# frontpanel.net
KiCad netlist of a schematic drawn in EAGLE
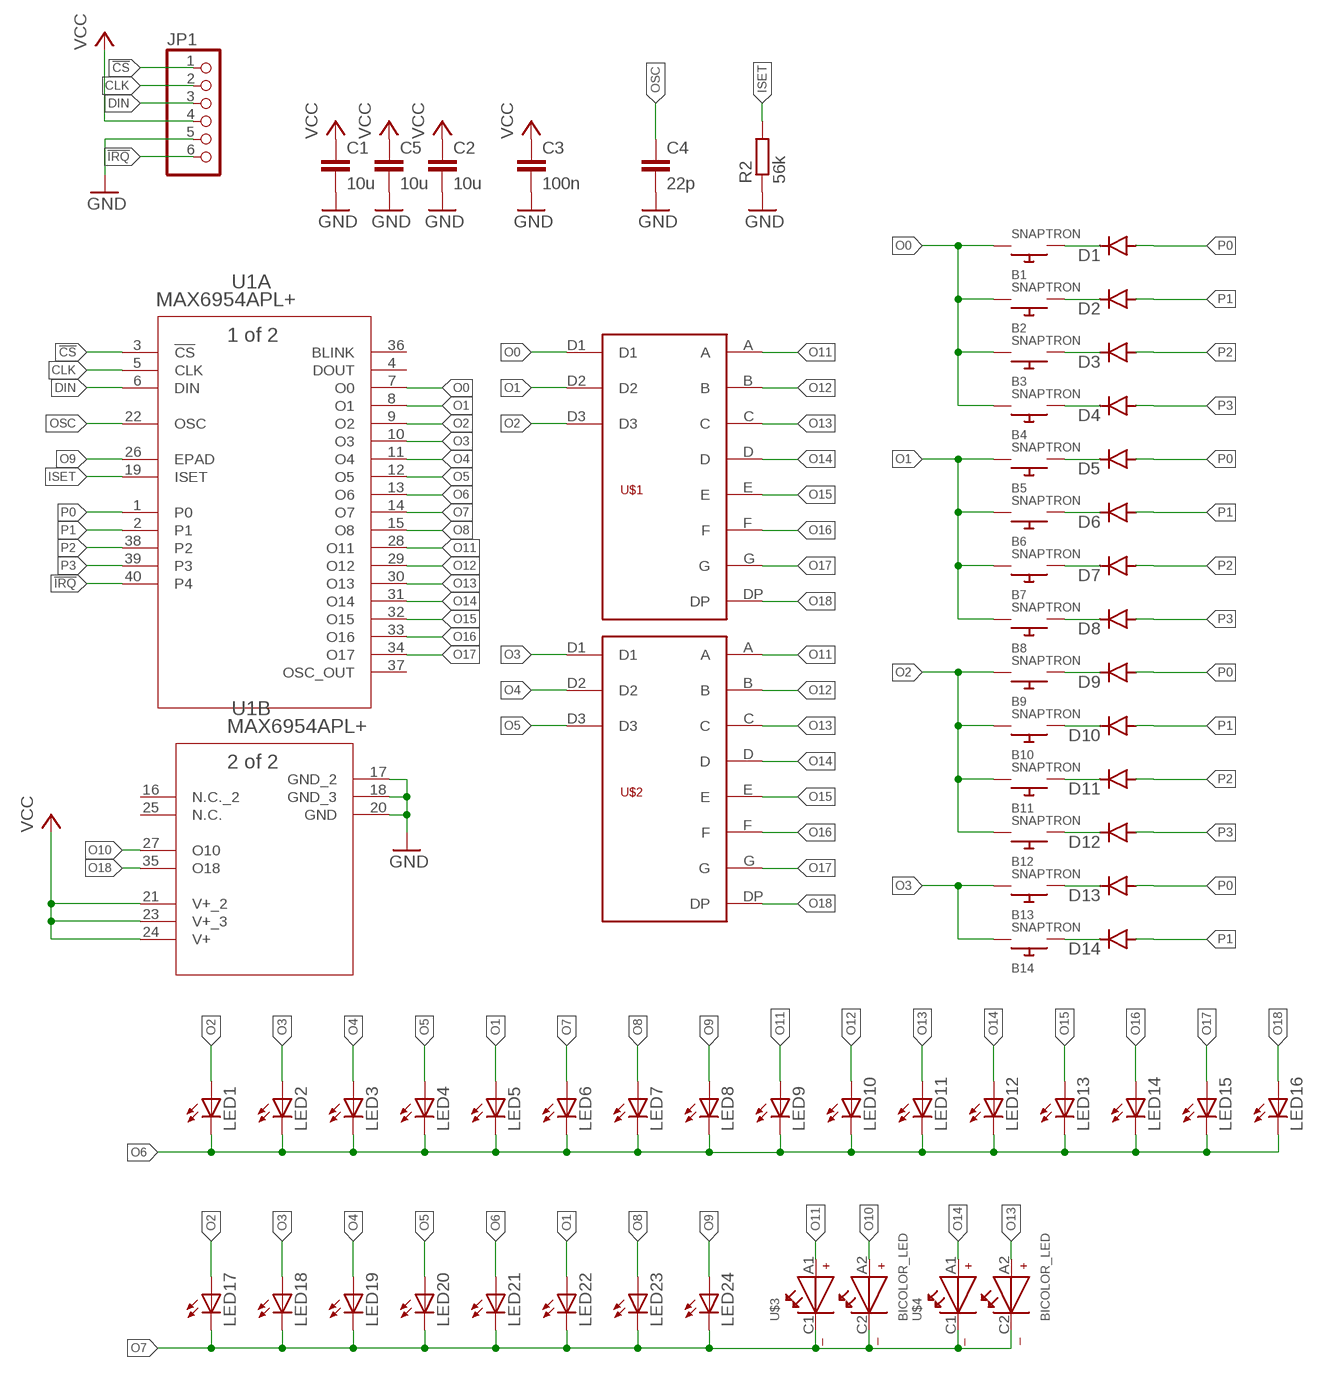
[diagram p0: schematic, sheet 1]

(export (version "E")
  (design (tool "Eeschema 10.0.6"))
  (components
    (comp (ref "B1")
      (value "SNAPTRON")
      (footprint "eagle-import:SNAPTRON-8.5")
      (libsource (lib "eagle-import") (part "SNAPTRON"))
    )
    (comp (ref "B2")
      (value "SNAPTRON")
      (footprint "eagle-import:SNAPTRON-8.5")
      (libsource (lib "eagle-import") (part "SNAPTRON"))
    )
    (comp (ref "B3")
      (value "SNAPTRON")
      (footprint "eagle-import:SNAPTRON-8.5")
      (libsource (lib "eagle-import") (part "SNAPTRON"))
    )
    (comp (ref "B4")
      (value "SNAPTRON")
      (footprint "eagle-import:SNAPTRON-8.5")
      (libsource (lib "eagle-import") (part "SNAPTRON"))
    )
    (comp (ref "B5")
      (value "SNAPTRON")
      (footprint "eagle-import:SNAPTRON-8.5")
      (libsource (lib "eagle-import") (part "SNAPTRON"))
    )
    (comp (ref "B6")
      (value "SNAPTRON")
      (footprint "eagle-import:SNAPTRON-8.5")
      (libsource (lib "eagle-import") (part "SNAPTRON"))
    )
    (comp (ref "B7")
      (value "SNAPTRON")
      (footprint "eagle-import:SNAPTRON-8.5")
      (libsource (lib "eagle-import") (part "SNAPTRON"))
    )
    (comp (ref "B8")
      (value "SNAPTRON")
      (footprint "eagle-import:SNAPTRON-8.5")
      (libsource (lib "eagle-import") (part "SNAPTRON"))
    )
    (comp (ref "B9")
      (value "SNAPTRON")
      (footprint "eagle-import:SNAPTRON-8.5")
      (libsource (lib "eagle-import") (part "SNAPTRON"))
    )
    (comp (ref "B10")
      (value "SNAPTRON")
      (footprint "eagle-import:SNAPTRON-8.5")
      (libsource (lib "eagle-import") (part "SNAPTRON"))
    )
    (comp (ref "B11")
      (value "SNAPTRON")
      (footprint "eagle-import:SNAPTRON-8.5")
      (libsource (lib "eagle-import") (part "SNAPTRON"))
    )
    (comp (ref "B12")
      (value "SNAPTRON")
      (footprint "eagle-import:SNAPTRON-8.5")
      (libsource (lib "eagle-import") (part "SNAPTRON"))
    )
    (comp (ref "B13")
      (value "SNAPTRON")
      (footprint "eagle-import:SNAPTRON-8.5")
      (libsource (lib "eagle-import") (part "SNAPTRON"))
    )
    (comp (ref "B14")
      (value "SNAPTRON")
      (footprint "eagle-import:SNAPTRON-8.5")
      (libsource (lib "eagle-import") (part "SNAPTRON"))
    )
    (comp (ref "C1")
      (value "10u")
      (footprint "eagle-import:C0805")
      (libsource (lib "eagle-import") (part "C-EUC0805"))
    )
    (comp (ref "C2")
      (value "10u")
      (footprint "eagle-import:C0805")
      (libsource (lib "eagle-import") (part "C-EUC0805"))
    )
    (comp (ref "C3")
      (value "100n")
      (footprint "eagle-import:C0805")
      (libsource (lib "eagle-import") (part "C-EUC0805"))
    )
    (comp (ref "C4")
      (value "22p")
      (footprint "eagle-import:C0805")
      (libsource (lib "eagle-import") (part "C-EUC0805"))
    )
    (comp (ref "C5")
      (value "10u")
      (footprint "eagle-import:C0805")
      (libsource (lib "eagle-import") (part "C-EUC0805"))
    )
    (comp (ref "D1")
      (value "1N4148DO35-10")
      (footprint "eagle-import:DO35-10")
      (libsource (lib "eagle-import") (part "1N4148DO35-10"))
    )
    (comp (ref "D2")
      (value "1N4148DO35-10")
      (footprint "eagle-import:DO35-10")
      (libsource (lib "eagle-import") (part "1N4148DO35-10"))
    )
    (comp (ref "D3")
      (value "1N4148DO35-10")
      (footprint "eagle-import:DO35-10")
      (libsource (lib "eagle-import") (part "1N4148DO35-10"))
    )
    (comp (ref "D4")
      (value "1N4148DO35-10")
      (footprint "eagle-import:DO35-10")
      (libsource (lib "eagle-import") (part "1N4148DO35-10"))
    )
    (comp (ref "D5")
      (value "1N4148DO35-10")
      (footprint "eagle-import:DO35-10")
      (libsource (lib "eagle-import") (part "1N4148DO35-10"))
    )
    (comp (ref "D6")
      (value "1N4148DO35-10")
      (footprint "eagle-import:DO35-10")
      (libsource (lib "eagle-import") (part "1N4148DO35-10"))
    )
    (comp (ref "D7")
      (value "1N4148DO35-10")
      (footprint "eagle-import:DO35-10")
      (libsource (lib "eagle-import") (part "1N4148DO35-10"))
    )
    (comp (ref "D8")
      (value "1N4148DO35-10")
      (footprint "eagle-import:DO35-10")
      (libsource (lib "eagle-import") (part "1N4148DO35-10"))
    )
    (comp (ref "D9")
      (value "1N4148DO35-10")
      (footprint "eagle-import:DO35-10")
      (libsource (lib "eagle-import") (part "1N4148DO35-10"))
    )
    (comp (ref "D10")
      (value "1N4148DO35-10")
      (footprint "eagle-import:DO35-10")
      (libsource (lib "eagle-import") (part "1N4148DO35-10"))
    )
    (comp (ref "D11")
      (value "1N4148DO35-10")
      (footprint "eagle-import:DO35-10")
      (libsource (lib "eagle-import") (part "1N4148DO35-10"))
    )
    (comp (ref "D12")
      (value "1N4148DO35-10")
      (footprint "eagle-import:DO35-10")
      (libsource (lib "eagle-import") (part "1N4148DO35-10"))
    )
    (comp (ref "D13")
      (value "1N4148DO35-10")
      (footprint "eagle-import:DO35-10")
      (libsource (lib "eagle-import") (part "1N4148DO35-10"))
    )
    (comp (ref "D14")
      (value "1N4148DO35-10")
      (footprint "eagle-import:DO35-10")
      (libsource (lib "eagle-import") (part "1N4148DO35-10"))
    )
    (comp (ref "JP1")
      (value "PINHD-1X6")
      (footprint "eagle-import:1X06")
      (libsource (lib "eagle-import") (part "PINHD-1X6"))
    )
    (comp (ref "LED1")
      (value "LEDCHIP-LED0805")
      (footprint "eagle-import:CHIP-LED0805")
      (libsource (lib "eagle-import") (part "LEDCHIP-LED0805"))
    )
    (comp (ref "LED2")
      (value "LEDCHIP-LED0805")
      (footprint "eagle-import:CHIP-LED0805")
      (libsource (lib "eagle-import") (part "LEDCHIP-LED0805"))
    )
    (comp (ref "LED3")
      (value "LEDCHIP-LED0805")
      (footprint "eagle-import:CHIP-LED0805")
      (libsource (lib "eagle-import") (part "LEDCHIP-LED0805"))
    )
    (comp (ref "LED4")
      (value "LEDCHIP-LED0805")
      (footprint "eagle-import:CHIP-LED0805")
      (libsource (lib "eagle-import") (part "LEDCHIP-LED0805"))
    )
    (comp (ref "LED5")
      (value "LEDCHIP-LED0805")
      (footprint "eagle-import:CHIP-LED0805")
      (libsource (lib "eagle-import") (part "LEDCHIP-LED0805"))
    )
    (comp (ref "LED6")
      (value "LEDCHIP-LED0805")
      (footprint "eagle-import:CHIP-LED0805")
      (libsource (lib "eagle-import") (part "LEDCHIP-LED0805"))
    )
    (comp (ref "LED7")
      (value "LEDCHIP-LED0805")
      (footprint "eagle-import:CHIP-LED0805")
      (libsource (lib "eagle-import") (part "LEDCHIP-LED0805"))
    )
    (comp (ref "LED8")
      (value "LEDCHIP-LED0805")
      (footprint "eagle-import:CHIP-LED0805")
      (libsource (lib "eagle-import") (part "LEDCHIP-LED0805"))
    )
    (comp (ref "LED9")
      (value "LEDCHIP-LED0805")
      (footprint "eagle-import:CHIP-LED0805")
      (libsource (lib "eagle-import") (part "LEDCHIP-LED0805"))
    )
    (comp (ref "LED10")
      (value "LEDCHIP-LED0805")
      (footprint "eagle-import:CHIP-LED0805")
      (libsource (lib "eagle-import") (part "LEDCHIP-LED0805"))
    )
    (comp (ref "LED11")
      (value "LEDCHIP-LED0805")
      (footprint "eagle-import:CHIP-LED0805")
      (libsource (lib "eagle-import") (part "LEDCHIP-LED0805"))
    )
    (comp (ref "LED12")
      (value "LEDCHIP-LED0805")
      (footprint "eagle-import:CHIP-LED0805")
      (libsource (lib "eagle-import") (part "LEDCHIP-LED0805"))
    )
    (comp (ref "LED13")
      (value "LEDCHIP-LED0805")
      (footprint "eagle-import:CHIP-LED0805")
      (libsource (lib "eagle-import") (part "LEDCHIP-LED0805"))
    )
    (comp (ref "LED14")
      (value "LEDCHIP-LED0805")
      (footprint "eagle-import:CHIP-LED0805")
      (libsource (lib "eagle-import") (part "LEDCHIP-LED0805"))
    )
    (comp (ref "LED15")
      (value "LEDCHIP-LED0805")
      (footprint "eagle-import:CHIP-LED0805")
      (libsource (lib "eagle-import") (part "LEDCHIP-LED0805"))
    )
    (comp (ref "LED16")
      (value "LEDCHIP-LED0805")
      (footprint "eagle-import:CHIP-LED0805")
      (libsource (lib "eagle-import") (part "LEDCHIP-LED0805"))
    )
    (comp (ref "LED17")
      (value "LEDCHIP-LED0805")
      (footprint "eagle-import:CHIP-LED0805")
      (libsource (lib "eagle-import") (part "LEDCHIP-LED0805"))
    )
    (comp (ref "LED18")
      (value "LEDCHIP-LED0805")
      (footprint "eagle-import:CHIP-LED0805")
      (libsource (lib "eagle-import") (part "LEDCHIP-LED0805"))
    )
    (comp (ref "LED19")
      (value "LEDCHIP-LED0805")
      (footprint "eagle-import:CHIP-LED0805")
      (libsource (lib "eagle-import") (part "LEDCHIP-LED0805"))
    )
    (comp (ref "LED20")
      (value "LEDCHIP-LED0805")
      (footprint "eagle-import:CHIP-LED0805")
      (libsource (lib "eagle-import") (part "LEDCHIP-LED0805"))
    )
    (comp (ref "LED21")
      (value "LEDCHIP-LED0805")
      (footprint "eagle-import:CHIP-LED0805")
      (libsource (lib "eagle-import") (part "LEDCHIP-LED0805"))
    )
    (comp (ref "LED22")
      (value "LEDCHIP-LED0805")
      (footprint "eagle-import:CHIP-LED0805")
      (libsource (lib "eagle-import") (part "LEDCHIP-LED0805"))
    )
    (comp (ref "LED23")
      (value "LEDCHIP-LED0805")
      (footprint "eagle-import:CHIP-LED0805")
      (libsource (lib "eagle-import") (part "LEDCHIP-LED0805"))
    )
    (comp (ref "LED24")
      (value "LEDCHIP-LED0805")
      (footprint "eagle-import:CHIP-LED0805")
      (libsource (lib "eagle-import") (part "LEDCHIP-LED0805"))
    )
    (comp (ref "R2")
      (value "56k")
      (footprint "eagle-import:R0805")
      (libsource (lib "eagle-import") (part "R-EU_R0805"))
    )
    (comp (ref "U$1")
      (value "3-DIGIT_7-SEGMENT-DISPLAY")
      (footprint "eagle-import:3-DIGIT_7-SEGMENT-DISPLAY")
      (libsource (lib "eagle-import") (part "3-DIGIT_7-SEGMENT-DISPLAY"))
    )
    (comp (ref "U$2")
      (value "3-DIGIT_7-SEGMENT-DISPLAY")
      (footprint "eagle-import:3-DIGIT_7-SEGMENT-DISPLAY")
      (libsource (lib "eagle-import") (part "3-DIGIT_7-SEGMENT-DISPLAY"))
    )
    (comp (ref "U$3")
      (value "BICOLOR_LED")
      (footprint "eagle-import:BICOLOR_LED")
      (libsource (lib "eagle-import") (part "BICOLOR_LED"))
    )
    (comp (ref "U$4")
      (value "BICOLOR_LED")
      (footprint "eagle-import:BICOLOR_LED")
      (libsource (lib "eagle-import") (part "BICOLOR_LED"))
    )
    (comp (ref "U1")
      (value "MAX6954APL+")
      (footprint "eagle-import:21-0044B_40_MXM")
      (libsource (lib "eagle-import") (part "MAX6954APL+"))
    )
  )
  (nets
    (net (code "1") (name "/~{CS}") (class "Default")
      (node (ref "JP1") (pin "1") (pinfunction "1_1") (pintype "passive"))
      (node (ref "U1") (pin "3") (pinfunction "~{CS}_3") (pintype "input"))
    )
    (net (code "2") (name "/~{IRQ}") (class "Default")
      (node (ref "JP1") (pin "6") (pinfunction "6_6") (pintype "passive"))
      (node (ref "U1") (pin "40") (pinfunction "P4_40") (pintype "bidirectional"))
    )
    (net (code "3") (name "CLK") (class "Default")
      (node (ref "JP1") (pin "2") (pinfunction "2_2") (pintype "passive"))
      (node (ref "U1") (pin "5") (pinfunction "CLK_5") (pintype "input"))
    )
    (net (code "4") (name "DIN") (class "Default")
      (node (ref "JP1") (pin "3") (pinfunction "3_3") (pintype "passive"))
      (node (ref "U1") (pin "6") (pinfunction "DIN_6") (pintype "input"))
    )
    (net (code "5") (name "GND") (class "Default")
      (node (ref "C1") (pin "2") (pinfunction "2_2") (pintype "passive"))
      (node (ref "C2") (pin "2") (pinfunction "2_2") (pintype "passive"))
      (node (ref "C3") (pin "2") (pinfunction "2_2") (pintype "passive"))
      (node (ref "C4") (pin "2") (pinfunction "2_2") (pintype "passive"))
      (node (ref "C5") (pin "2") (pinfunction "2_2") (pintype "passive"))
      (node (ref "JP1") (pin "5") (pinfunction "5_5") (pintype "passive"))
      (node (ref "R2") (pin "1") (pinfunction "1_1") (pintype "passive"))
      (node (ref "U1") (pin "17") (pinfunction "GND_2_17") (pintype "power_in"))
      (node (ref "U1") (pin "18") (pinfunction "GND_3_18") (pintype "power_in"))
      (node (ref "U1") (pin "20") (pinfunction "GND_20") (pintype "power_in"))
    )
    (net (code "6") (name "ISET") (class "Default")
      (node (ref "R2") (pin "2") (pinfunction "2_2") (pintype "passive"))
      (node (ref "U1") (pin "19") (pinfunction "ISET_19") (pintype "passive"))
    )
    (net (code "7") (name "Net-(B1-PadP$2)") (class "Default")
      (node (ref "B1") (pin "P$2") (pinfunction "P$2_P$2") (pintype "passive"))
      (node (ref "D1") (pin "C") (pinfunction "C_C") (pintype "passive"))
    )
    (net (code "8") (name "Net-(B2-PadP$2)") (class "Default")
      (node (ref "B2") (pin "P$2") (pinfunction "P$2_P$2") (pintype "passive"))
      (node (ref "D2") (pin "C") (pinfunction "C_C") (pintype "passive"))
    )
    (net (code "9") (name "Net-(B3-PadP$2)") (class "Default")
      (node (ref "B3") (pin "P$2") (pinfunction "P$2_P$2") (pintype "passive"))
      (node (ref "D3") (pin "C") (pinfunction "C_C") (pintype "passive"))
    )
    (net (code "10") (name "Net-(B4-PadP$2)") (class "Default")
      (node (ref "B4") (pin "P$2") (pinfunction "P$2_P$2") (pintype "passive"))
      (node (ref "D4") (pin "C") (pinfunction "C_C") (pintype "passive"))
    )
    (net (code "11") (name "Net-(B5-PadP$2)") (class "Default")
      (node (ref "B5") (pin "P$2") (pinfunction "P$2_P$2") (pintype "passive"))
      (node (ref "D5") (pin "C") (pinfunction "C_C") (pintype "passive"))
    )
    (net (code "12") (name "Net-(B6-PadP$2)") (class "Default")
      (node (ref "B6") (pin "P$2") (pinfunction "P$2_P$2") (pintype "passive"))
      (node (ref "D6") (pin "C") (pinfunction "C_C") (pintype "passive"))
    )
    (net (code "13") (name "Net-(B7-PadP$2)") (class "Default")
      (node (ref "B7") (pin "P$2") (pinfunction "P$2_P$2") (pintype "passive"))
      (node (ref "D7") (pin "C") (pinfunction "C_C") (pintype "passive"))
    )
    (net (code "14") (name "Net-(B8-PadP$2)") (class "Default")
      (node (ref "B8") (pin "P$2") (pinfunction "P$2_P$2") (pintype "passive"))
      (node (ref "D8") (pin "C") (pinfunction "C_C") (pintype "passive"))
    )
    (net (code "15") (name "Net-(B9-PadP$2)") (class "Default")
      (node (ref "B9") (pin "P$2") (pinfunction "P$2_P$2") (pintype "passive"))
      (node (ref "D9") (pin "C") (pinfunction "C_C") (pintype "passive"))
    )
    (net (code "16") (name "Net-(B10-PadP$2)") (class "Default")
      (node (ref "B10") (pin "P$2") (pinfunction "P$2_P$2") (pintype "passive"))
      (node (ref "D10") (pin "C") (pinfunction "C_C") (pintype "passive"))
    )
    (net (code "17") (name "Net-(B11-PadP$2)") (class "Default")
      (node (ref "B11") (pin "P$2") (pinfunction "P$2_P$2") (pintype "passive"))
      (node (ref "D11") (pin "C") (pinfunction "C_C") (pintype "passive"))
    )
    (net (code "18") (name "Net-(B12-PadP$2)") (class "Default")
      (node (ref "B12") (pin "P$2") (pinfunction "P$2_P$2") (pintype "passive"))
      (node (ref "D12") (pin "C") (pinfunction "C_C") (pintype "passive"))
    )
    (net (code "19") (name "Net-(B13-PadP$2)") (class "Default")
      (node (ref "B13") (pin "P$2") (pinfunction "P$2_P$2") (pintype "passive"))
      (node (ref "D13") (pin "C") (pinfunction "C_C") (pintype "passive"))
    )
    (net (code "20") (name "Net-(B14-PadP$2)") (class "Default")
      (node (ref "B14") (pin "P$2") (pinfunction "P$2_P$2") (pintype "passive"))
      (node (ref "D14") (pin "C") (pinfunction "C_C") (pintype "passive"))
    )
    (net (code "21") (name "O0") (class "Default")
      (node (ref "B1") (pin "P$1") (pinfunction "P$1_P$1") (pintype "passive"))
      (node (ref "B2") (pin "P$1") (pinfunction "P$1_P$1") (pintype "passive"))
      (node (ref "B3") (pin "P$1") (pinfunction "P$1_P$1") (pintype "passive"))
      (node (ref "B4") (pin "P$1") (pinfunction "P$1_P$1") (pintype "passive"))
      (node (ref "U$1") (pin "D1") (pinfunction "D1_D1") (pintype "bidirectional"))
      (node (ref "U1") (pin "7") (pinfunction "O0_7") (pintype "output"))
    )
    (net (code "22") (name "O1") (class "Default")
      (node (ref "B5") (pin "P$1") (pinfunction "P$1_P$1") (pintype "passive"))
      (node (ref "B6") (pin "P$1") (pinfunction "P$1_P$1") (pintype "passive"))
      (node (ref "B7") (pin "P$1") (pinfunction "P$1_P$1") (pintype "passive"))
      (node (ref "B8") (pin "P$1") (pinfunction "P$1_P$1") (pintype "passive"))
      (node (ref "LED22") (pin "A") (pinfunction "A_A") (pintype "passive"))
      (node (ref "LED5") (pin "A") (pinfunction "A_A") (pintype "passive"))
      (node (ref "U$1") (pin "D2") (pinfunction "D2_D2") (pintype "bidirectional"))
      (node (ref "U1") (pin "8") (pinfunction "O1_8") (pintype "output"))
    )
    (net (code "23") (name "O2") (class "Default")
      (node (ref "B10") (pin "P$1") (pinfunction "P$1_P$1") (pintype "passive"))
      (node (ref "B11") (pin "P$1") (pinfunction "P$1_P$1") (pintype "passive"))
      (node (ref "B12") (pin "P$1") (pinfunction "P$1_P$1") (pintype "passive"))
      (node (ref "B9") (pin "P$1") (pinfunction "P$1_P$1") (pintype "passive"))
      (node (ref "LED1") (pin "A") (pinfunction "A_A") (pintype "passive"))
      (node (ref "LED17") (pin "A") (pinfunction "A_A") (pintype "passive"))
      (node (ref "U$1") (pin "D3") (pinfunction "D3_D3") (pintype "bidirectional"))
      (node (ref "U1") (pin "9") (pinfunction "O2_9") (pintype "output"))
    )
    (net (code "24") (name "O3") (class "Default")
      (node (ref "B13") (pin "P$1") (pinfunction "P$1_P$1") (pintype "passive"))
      (node (ref "B14") (pin "P$1") (pinfunction "P$1_P$1") (pintype "passive"))
      (node (ref "LED18") (pin "A") (pinfunction "A_A") (pintype "passive"))
      (node (ref "LED2") (pin "A") (pinfunction "A_A") (pintype "passive"))
      (node (ref "U$2") (pin "D1") (pinfunction "D1_D1") (pintype "bidirectional"))
      (node (ref "U1") (pin "10") (pinfunction "O3_10") (pintype "output"))
    )
    (net (code "25") (name "O4") (class "Default")
      (node (ref "LED19") (pin "A") (pinfunction "A_A") (pintype "passive"))
      (node (ref "LED3") (pin "A") (pinfunction "A_A") (pintype "passive"))
      (node (ref "U$2") (pin "D2") (pinfunction "D2_D2") (pintype "bidirectional"))
      (node (ref "U1") (pin "11") (pinfunction "O4_11") (pintype "output"))
    )
    (net (code "26") (name "O5") (class "Default")
      (node (ref "LED20") (pin "A") (pinfunction "A_A") (pintype "passive"))
      (node (ref "LED4") (pin "A") (pinfunction "A_A") (pintype "passive"))
      (node (ref "U$2") (pin "D3") (pinfunction "D3_D3") (pintype "bidirectional"))
      (node (ref "U1") (pin "12") (pinfunction "O5_12") (pintype "output"))
    )
    (net (code "27") (name "O6") (class "Default")
      (node (ref "LED1") (pin "C") (pinfunction "C_C") (pintype "passive"))
      (node (ref "LED10") (pin "C") (pinfunction "C_C") (pintype "passive"))
      (node (ref "LED11") (pin "C") (pinfunction "C_C") (pintype "passive"))
      (node (ref "LED12") (pin "C") (pinfunction "C_C") (pintype "passive"))
      (node (ref "LED13") (pin "C") (pinfunction "C_C") (pintype "passive"))
      (node (ref "LED14") (pin "C") (pinfunction "C_C") (pintype "passive"))
      (node (ref "LED15") (pin "C") (pinfunction "C_C") (pintype "passive"))
      (node (ref "LED16") (pin "C") (pinfunction "C_C") (pintype "passive"))
      (node (ref "LED2") (pin "C") (pinfunction "C_C") (pintype "passive"))
      (node (ref "LED21") (pin "A") (pinfunction "A_A") (pintype "passive"))
      (node (ref "LED3") (pin "C") (pinfunction "C_C") (pintype "passive"))
      (node (ref "LED4") (pin "C") (pinfunction "C_C") (pintype "passive"))
      (node (ref "LED5") (pin "C") (pinfunction "C_C") (pintype "passive"))
      (node (ref "LED6") (pin "C") (pinfunction "C_C") (pintype "passive"))
      (node (ref "LED7") (pin "C") (pinfunction "C_C") (pintype "passive"))
      (node (ref "LED8") (pin "C") (pinfunction "C_C") (pintype "passive"))
      (node (ref "LED9") (pin "C") (pinfunction "C_C") (pintype "passive"))
      (node (ref "U1") (pin "13") (pinfunction "O6_13") (pintype "output"))
    )
    (net (code "28") (name "O7") (class "Default")
      (node (ref "LED17") (pin "C") (pinfunction "C_C") (pintype "passive"))
      (node (ref "LED18") (pin "C") (pinfunction "C_C") (pintype "passive"))
      (node (ref "LED19") (pin "C") (pinfunction "C_C") (pintype "passive"))
      (node (ref "LED20") (pin "C") (pinfunction "C_C") (pintype "passive"))
      (node (ref "LED21") (pin "C") (pinfunction "C_C") (pintype "passive"))
      (node (ref "LED22") (pin "C") (pinfunction "C_C") (pintype "passive"))
      (node (ref "LED23") (pin "C") (pinfunction "C_C") (pintype "passive"))
      (node (ref "LED24") (pin "C") (pinfunction "C_C") (pintype "passive"))
      (node (ref "LED6") (pin "A") (pinfunction "A_A") (pintype "passive"))
      (node (ref "U$3") (pin "C1") (pinfunction "C1_C1") (pintype "passive"))
      (node (ref "U$3") (pin "C2") (pinfunction "C2_C2") (pintype "passive"))
      (node (ref "U$4") (pin "C1") (pinfunction "C1_C1") (pintype "passive"))
      (node (ref "U$4") (pin "C2") (pinfunction "C2_C2") (pintype "passive"))
      (node (ref "U1") (pin "14") (pinfunction "O7_14") (pintype "output"))
    )
    (net (code "29") (name "O8") (class "Default")
      (node (ref "LED23") (pin "A") (pinfunction "A_A") (pintype "passive"))
      (node (ref "LED7") (pin "A") (pinfunction "A_A") (pintype "passive"))
      (node (ref "U1") (pin "15") (pinfunction "O8_15") (pintype "output"))
    )
    (net (code "30") (name "O9") (class "Default")
      (node (ref "LED24") (pin "A") (pinfunction "A_A") (pintype "passive"))
      (node (ref "LED8") (pin "A") (pinfunction "A_A") (pintype "passive"))
      (node (ref "U1") (pin "26") (pinfunction "EPAD_26") (pintype "passive"))
    )
    (net (code "31") (name "O10") (class "Default")
      (node (ref "U$3") (pin "A2") (pinfunction "A2_A2") (pintype "passive"))
      (node (ref "U1") (pin "27") (pinfunction "O10_27") (pintype "power_in"))
    )
    (net (code "32") (name "O11") (class "Default")
      (node (ref "LED9") (pin "A") (pinfunction "A_A") (pintype "passive"))
      (node (ref "U$1") (pin "A") (pinfunction "A_A") (pintype "bidirectional"))
      (node (ref "U$2") (pin "A") (pinfunction "A_A") (pintype "bidirectional"))
      (node (ref "U$3") (pin "A1") (pinfunction "A1_A1") (pintype "passive"))
      (node (ref "U1") (pin "28") (pinfunction "O11_28") (pintype "output"))
    )
    (net (code "33") (name "O12") (class "Default")
      (node (ref "LED10") (pin "A") (pinfunction "A_A") (pintype "passive"))
      (node (ref "U$1") (pin "B") (pinfunction "B_B") (pintype "bidirectional"))
      (node (ref "U$2") (pin "B") (pinfunction "B_B") (pintype "bidirectional"))
      (node (ref "U1") (pin "29") (pinfunction "O12_29") (pintype "output"))
    )
    (net (code "34") (name "O13") (class "Default")
      (node (ref "LED11") (pin "A") (pinfunction "A_A") (pintype "passive"))
      (node (ref "U$1") (pin "C") (pinfunction "C_C") (pintype "bidirectional"))
      (node (ref "U$2") (pin "C") (pinfunction "C_C") (pintype "bidirectional"))
      (node (ref "U$4") (pin "A2") (pinfunction "A2_A2") (pintype "passive"))
      (node (ref "U1") (pin "30") (pinfunction "O13_30") (pintype "output"))
    )
    (net (code "35") (name "O14") (class "Default")
      (node (ref "LED12") (pin "A") (pinfunction "A_A") (pintype "passive"))
      (node (ref "U$1") (pin "D") (pinfunction "D_D") (pintype "bidirectional"))
      (node (ref "U$2") (pin "D") (pinfunction "D_D") (pintype "bidirectional"))
      (node (ref "U$4") (pin "A1") (pinfunction "A1_A1") (pintype "passive"))
      (node (ref "U1") (pin "31") (pinfunction "O14_31") (pintype "output"))
    )
    (net (code "36") (name "O15") (class "Default")
      (node (ref "LED13") (pin "A") (pinfunction "A_A") (pintype "passive"))
      (node (ref "U$1") (pin "E") (pinfunction "E_E") (pintype "bidirectional"))
      (node (ref "U$2") (pin "E") (pinfunction "E_E") (pintype "bidirectional"))
      (node (ref "U1") (pin "32") (pinfunction "O15_32") (pintype "output"))
    )
    (net (code "37") (name "O16") (class "Default")
      (node (ref "LED14") (pin "A") (pinfunction "A_A") (pintype "passive"))
      (node (ref "U$1") (pin "F") (pinfunction "F_F") (pintype "bidirectional"))
      (node (ref "U$2") (pin "F") (pinfunction "F_F") (pintype "bidirectional"))
      (node (ref "U1") (pin "33") (pinfunction "O16_33") (pintype "output"))
    )
    (net (code "38") (name "O17") (class "Default")
      (node (ref "LED15") (pin "A") (pinfunction "A_A") (pintype "passive"))
      (node (ref "U$1") (pin "G") (pinfunction "G_G") (pintype "bidirectional"))
      (node (ref "U$2") (pin "G") (pinfunction "G_G") (pintype "bidirectional"))
      (node (ref "U1") (pin "34") (pinfunction "O17_34") (pintype "output"))
    )
    (net (code "39") (name "O18") (class "Default")
      (node (ref "LED16") (pin "A") (pinfunction "A_A") (pintype "passive"))
      (node (ref "U$1") (pin "DP") (pinfunction "DP_DP") (pintype "bidirectional"))
      (node (ref "U$2") (pin "DP") (pinfunction "DP_DP") (pintype "bidirectional"))
      (node (ref "U1") (pin "35") (pinfunction "O18_35") (pintype "power_in"))
    )
    (net (code "40") (name "OSC") (class "Default")
      (node (ref "C4") (pin "1") (pinfunction "1_1") (pintype "passive"))
      (node (ref "U1") (pin "22") (pinfunction "OSC_22") (pintype "input"))
    )
    (net (code "41") (name "P0") (class "Default")
      (node (ref "D1") (pin "A") (pinfunction "A_A") (pintype "passive"))
      (node (ref "D13") (pin "A") (pinfunction "A_A") (pintype "passive"))
      (node (ref "D5") (pin "A") (pinfunction "A_A") (pintype "passive"))
      (node (ref "D9") (pin "A") (pinfunction "A_A") (pintype "passive"))
      (node (ref "U1") (pin "1") (pinfunction "P0_1") (pintype "bidirectional"))
    )
    (net (code "42") (name "P1") (class "Default")
      (node (ref "D10") (pin "A") (pinfunction "A_A") (pintype "passive"))
      (node (ref "D14") (pin "A") (pinfunction "A_A") (pintype "passive"))
      (node (ref "D2") (pin "A") (pinfunction "A_A") (pintype "passive"))
      (node (ref "D6") (pin "A") (pinfunction "A_A") (pintype "passive"))
      (node (ref "U1") (pin "2") (pinfunction "P1_2") (pintype "bidirectional"))
    )
    (net (code "43") (name "P2") (class "Default")
      (node (ref "D11") (pin "A") (pinfunction "A_A") (pintype "passive"))
      (node (ref "D3") (pin "A") (pinfunction "A_A") (pintype "passive"))
      (node (ref "D7") (pin "A") (pinfunction "A_A") (pintype "passive"))
      (node (ref "U1") (pin "38") (pinfunction "P2_38") (pintype "bidirectional"))
    )
    (net (code "44") (name "P3") (class "Default")
      (node (ref "D12") (pin "A") (pinfunction "A_A") (pintype "passive"))
      (node (ref "D4") (pin "A") (pinfunction "A_A") (pintype "passive"))
      (node (ref "D8") (pin "A") (pinfunction "A_A") (pintype "passive"))
      (node (ref "U1") (pin "39") (pinfunction "P3_39") (pintype "bidirectional"))
    )
    (net (code "45") (name "VCC") (class "Default")
      (node (ref "C1") (pin "1") (pinfunction "1_1") (pintype "passive"))
      (node (ref "C2") (pin "1") (pinfunction "1_1") (pintype "passive"))
      (node (ref "C3") (pin "1") (pinfunction "1_1") (pintype "passive"))
      (node (ref "C5") (pin "1") (pinfunction "1_1") (pintype "passive"))
      (node (ref "JP1") (pin "4") (pinfunction "4_4") (pintype "passive"))
      (node (ref "U1") (pin "21") (pinfunction "V+_2_21") (pintype "power_in"))
      (node (ref "U1") (pin "23") (pinfunction "V+_3_23") (pintype "power_in"))
      (node (ref "U1") (pin "24") (pinfunction "V+_24") (pintype "power_in"))
    )
    (net (code "46") (name "unconnected-(U1A-BLINK-Pad36)") (class "Default")
      (node (ref "U1") (pin "36") (pinfunction "BLINK_36") (pintype "output"))
    )
    (net (code "47") (name "unconnected-(U1A-DOUT-Pad4)") (class "Default")
      (node (ref "U1") (pin "4") (pinfunction "DOUT_4") (pintype "output"))
    )
    (net (code "48") (name "unconnected-(U1A-OSC_OUT-Pad37)") (class "Default")
      (node (ref "U1") (pin "37") (pinfunction "OSC_OUT_37") (pintype "output"))
    )
    (net (code "49") (name "unconnected-(U1B-N.C.-Pad25)") (class "Default")
      (node (ref "U1") (pin "25") (pinfunction "N.C._25") (pintype "no_connect"))
    )
    (net (code "50") (name "unconnected-(U1B-N.C._2-Pad16)") (class "Default")
      (node (ref "U1") (pin "16") (pinfunction "N.C._2_16") (pintype "no_connect"))
    )
  )
)
